# eBike_Controller_v2.net
KiCad netlist of a schematic drawn in EAGLE
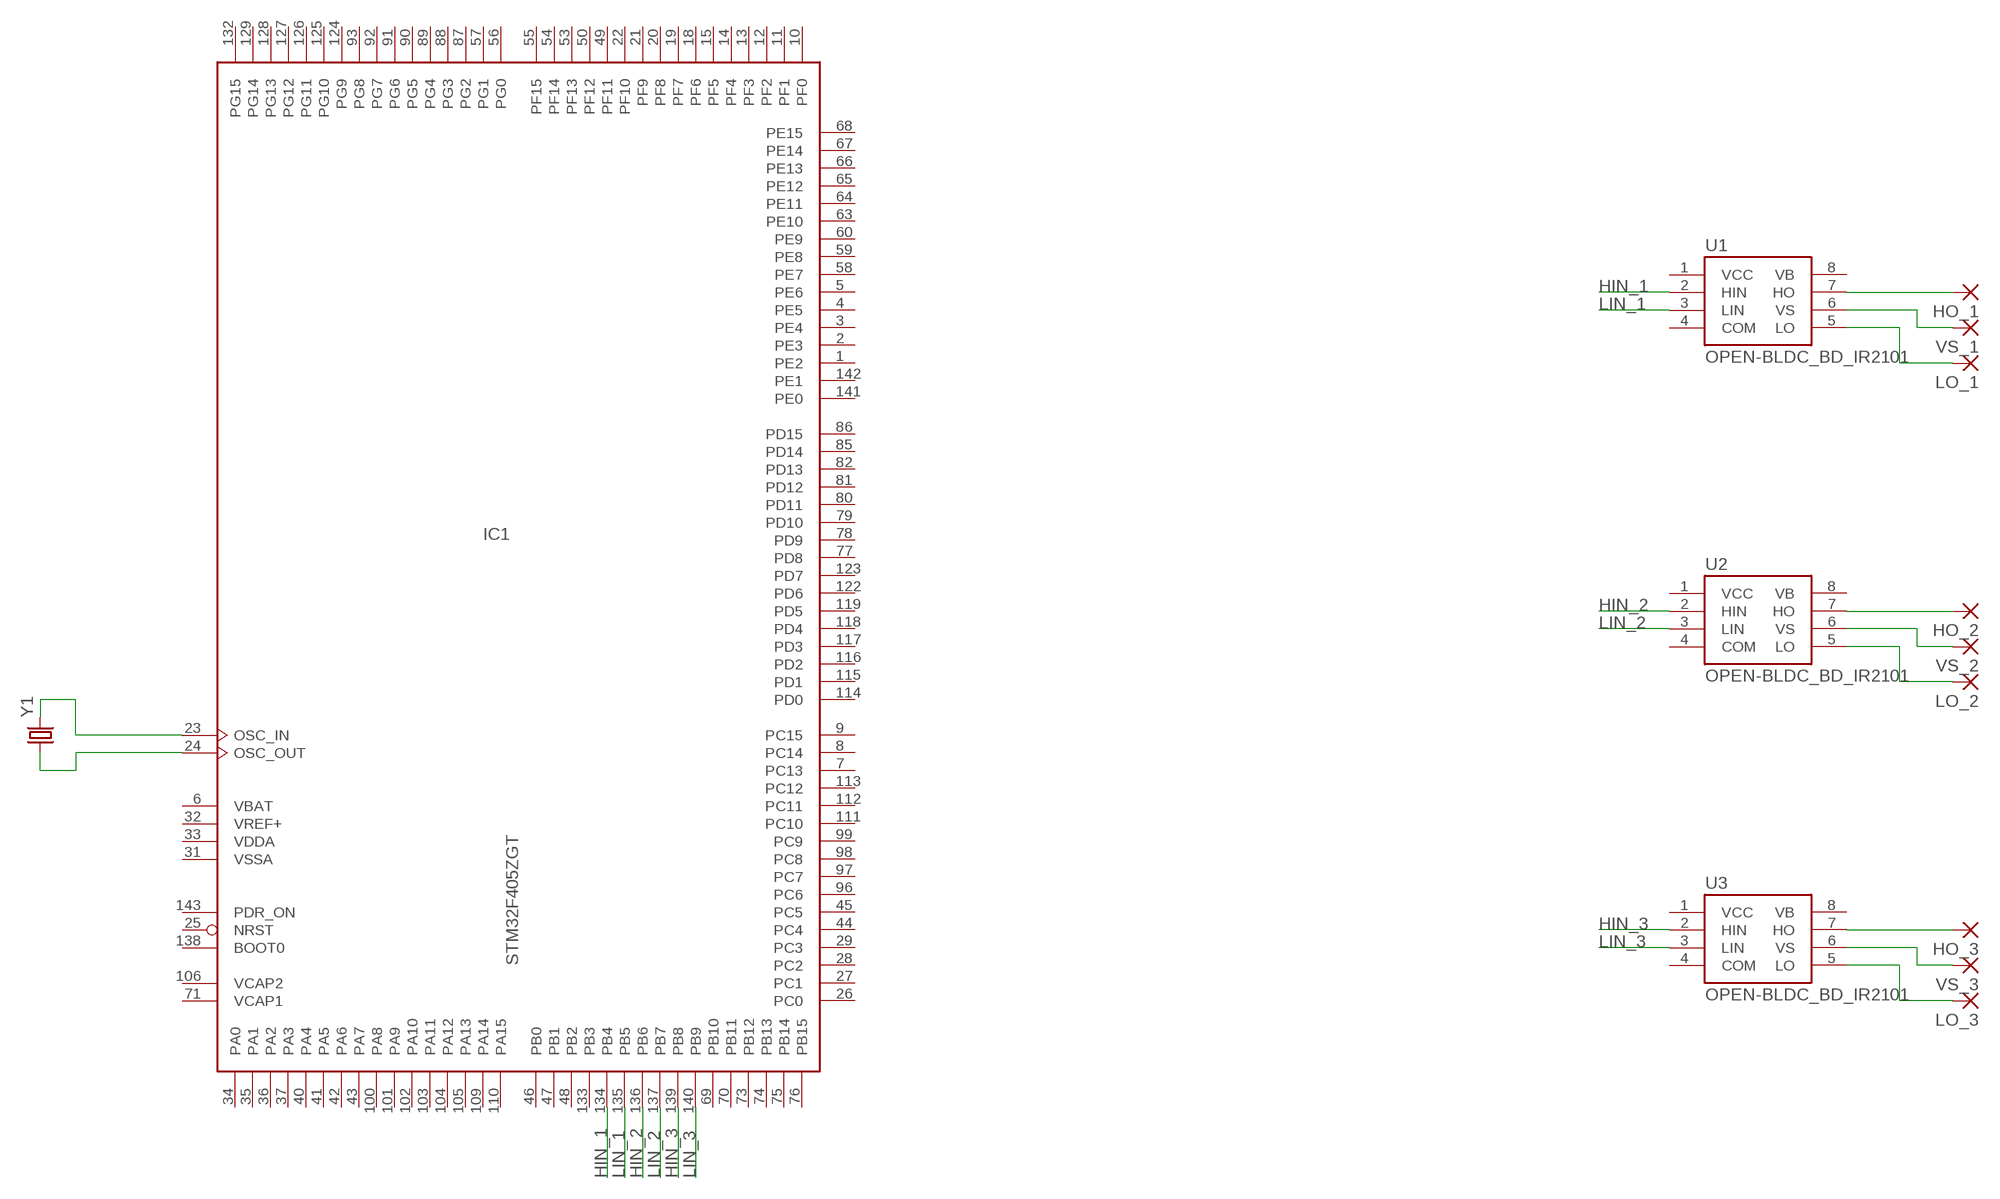
[diagram p0: schematic, sheet 1]

(export (version "E")
  (design (tool "Eeschema 10.0.6"))
  (components
    (comp (ref "HO_1")
      (value "3,81/1,4")
      (footprint "eagle-import:3,81_1,4")
      (libsource (lib "eagle-import") (part "3,81/1,4"))
    )
    (comp (ref "HO_2")
      (value "3,81/1,4")
      (footprint "eagle-import:3,81_1,4")
      (libsource (lib "eagle-import") (part "3,81/1,4"))
    )
    (comp (ref "HO_3")
      (value "3,81/1,4")
      (footprint "eagle-import:3,81_1,4")
      (libsource (lib "eagle-import") (part "3,81/1,4"))
    )
    (comp (ref "IC1")
      (value "STM32F405ZGT")
      (footprint "eagle-import:LQFP144")
      (libsource (lib "eagle-import") (part "STM32F405ZTG"))
    )
    (comp (ref "LO_1")
      (value "3,81/1,4")
      (footprint "eagle-import:3,81_1,4")
      (libsource (lib "eagle-import") (part "3,81/1,4"))
    )
    (comp (ref "LO_2")
      (value "3,81/1,4")
      (footprint "eagle-import:3,81_1,4")
      (libsource (lib "eagle-import") (part "3,81/1,4"))
    )
    (comp (ref "LO_3")
      (value "3,81/1,4")
      (footprint "eagle-import:3,81_1,4")
      (libsource (lib "eagle-import") (part "3,81/1,4"))
    )
    (comp (ref "U1")
      (value "OPEN-BLDC_BD_IR2101")
      (footprint "eagle-import:OPEN-BLDC_SO8")
      (libsource (lib "eagle-import") (part "OPEN-BLDC_BD_IR2101"))
    )
    (comp (ref "U2")
      (value "OPEN-BLDC_BD_IR2101")
      (footprint "eagle-import:OPEN-BLDC_SO8")
      (libsource (lib "eagle-import") (part "OPEN-BLDC_BD_IR2101"))
    )
    (comp (ref "U3")
      (value "OPEN-BLDC_BD_IR2101")
      (footprint "eagle-import:OPEN-BLDC_SO8")
      (libsource (lib "eagle-import") (part "OPEN-BLDC_BD_IR2101"))
    )
    (comp (ref "VS_1")
      (value "3,81/1,4")
      (footprint "eagle-import:3,81_1,4")
      (libsource (lib "eagle-import") (part "3,81/1,4"))
    )
    (comp (ref "VS_2")
      (value "3,81/1,4")
      (footprint "eagle-import:3,81_1,4")
      (libsource (lib "eagle-import") (part "3,81/1,4"))
    )
    (comp (ref "VS_3")
      (value "3,81/1,4")
      (footprint "eagle-import:3,81_1,4")
      (libsource (lib "eagle-import") (part "3,81/1,4"))
    )
    (comp (ref "Y1")
      (value "CRYSTALHC49US")
      (footprint "eagle-import:HC49US")
      (libsource (lib "eagle-import") (part "CRYSTALHC49US"))
    )
  )
  (nets
    (net (code "1") (name "/HIN_1") (class "Default")
      (node (ref "IC1") (pin "134") (pinfunction "PB4_134") (pintype "bidirectional"))
      (node (ref "U1") (pin "2") (pinfunction "HIN_2") (pintype "bidirectional"))
    )
    (net (code "2") (name "/HIN_2") (class "Default")
      (node (ref "IC1") (pin "136") (pinfunction "PB6_136") (pintype "bidirectional"))
      (node (ref "U2") (pin "2") (pinfunction "HIN_2") (pintype "bidirectional"))
    )
    (net (code "3") (name "/HIN_3") (class "Default")
      (node (ref "IC1") (pin "139") (pinfunction "PB8_139") (pintype "bidirectional"))
      (node (ref "U3") (pin "2") (pinfunction "HIN_2") (pintype "bidirectional"))
    )
    (net (code "4") (name "/LIN_1") (class "Default")
      (node (ref "IC1") (pin "135") (pinfunction "PB5_135") (pintype "bidirectional"))
      (node (ref "U1") (pin "3") (pinfunction "LIN_3") (pintype "bidirectional"))
    )
    (net (code "5") (name "/LIN_2") (class "Default")
      (node (ref "IC1") (pin "137") (pinfunction "PB7_137") (pintype "bidirectional"))
      (node (ref "U2") (pin "3") (pinfunction "LIN_3") (pintype "bidirectional"))
    )
    (net (code "6") (name "/LIN_3") (class "Default")
      (node (ref "IC1") (pin "140") (pinfunction "PB9_140") (pintype "bidirectional"))
      (node (ref "U3") (pin "3") (pinfunction "LIN_3") (pintype "bidirectional"))
    )
    (net (code "7") (name "/VBAT") (class "Default")
      (node (ref "IC1") (pin "6") (pinfunction "VBAT_6") (pintype "power_in"))
    )
    (net (code "8") (name "/VCAP1") (class "Default")
      (node (ref "IC1") (pin "71") (pinfunction "VCAP1_71") (pintype "power_in"))
    )
    (net (code "9") (name "/VCAP2") (class "Default")
      (node (ref "IC1") (pin "106") (pinfunction "VCAP2_106") (pintype "power_in"))
    )
    (net (code "10") (name "/VDDA") (class "Default")
      (node (ref "IC1") (pin "33") (pinfunction "VDDA_33") (pintype "power_in"))
    )
    (net (code "11") (name "/VREF+") (class "Default")
      (node (ref "IC1") (pin "32") (pinfunction "VREF+_32") (pintype "power_in"))
    )
    (net (code "12") (name "/VSSA") (class "Default")
      (node (ref "IC1") (pin "31") (pinfunction "VSSA_31") (pintype "power_in"))
    )
    (net (code "13") (name "Net-(HO_1-P)") (class "Default")
      (node (ref "HO_1") (pin "1") (pinfunction "P_1") (pintype "passive"))
      (node (ref "U1") (pin "7") (pinfunction "HO_7") (pintype "bidirectional"))
    )
    (net (code "14") (name "Net-(HO_2-P)") (class "Default")
      (node (ref "HO_2") (pin "1") (pinfunction "P_1") (pintype "passive"))
      (node (ref "U2") (pin "7") (pinfunction "HO_7") (pintype "bidirectional"))
    )
    (net (code "15") (name "Net-(HO_3-P)") (class "Default")
      (node (ref "HO_3") (pin "1") (pinfunction "P_1") (pintype "passive"))
      (node (ref "U3") (pin "7") (pinfunction "HO_7") (pintype "bidirectional"))
    )
    (net (code "16") (name "Net-(IC1A-OSC_IN)") (class "Default")
      (node (ref "IC1") (pin "23") (pinfunction "OSC_IN_23") (pintype "bidirectional"))
      (node (ref "Y1") (pin "2") (pinfunction "2_2") (pintype "passive"))
    )
    (net (code "17") (name "Net-(IC1A-OSC_OUT)") (class "Default")
      (node (ref "IC1") (pin "24") (pinfunction "OSC_OUT_24") (pintype "bidirectional"))
      (node (ref "Y1") (pin "1") (pinfunction "1_1") (pintype "passive"))
    )
    (net (code "18") (name "Net-(LO_1-P)") (class "Default")
      (node (ref "LO_1") (pin "1") (pinfunction "P_1") (pintype "passive"))
      (node (ref "U1") (pin "5") (pinfunction "LO_5") (pintype "bidirectional"))
    )
    (net (code "19") (name "Net-(LO_2-P)") (class "Default")
      (node (ref "LO_2") (pin "1") (pinfunction "P_1") (pintype "passive"))
      (node (ref "U2") (pin "5") (pinfunction "LO_5") (pintype "bidirectional"))
    )
    (net (code "20") (name "Net-(LO_3-P)") (class "Default")
      (node (ref "LO_3") (pin "1") (pinfunction "P_1") (pintype "passive"))
      (node (ref "U3") (pin "5") (pinfunction "LO_5") (pintype "bidirectional"))
    )
    (net (code "21") (name "Net-(U1-VS)") (class "Default")
      (node (ref "U1") (pin "6") (pinfunction "VS_6") (pintype "bidirectional"))
      (node (ref "VS_1") (pin "1") (pinfunction "P_1") (pintype "passive"))
    )
    (net (code "22") (name "Net-(U2-VS)") (class "Default")
      (node (ref "U2") (pin "6") (pinfunction "VS_6") (pintype "bidirectional"))
      (node (ref "VS_2") (pin "1") (pinfunction "P_1") (pintype "passive"))
    )
    (net (code "23") (name "Net-(U3-VS)") (class "Default")
      (node (ref "U3") (pin "6") (pinfunction "VS_6") (pintype "bidirectional"))
      (node (ref "VS_3") (pin "1") (pinfunction "P_1") (pintype "passive"))
    )
    (net (code "24") (name "unconnected-(IC1A-BOOT0-Pad138)") (class "Default")
      (node (ref "IC1") (pin "138") (pinfunction "BOOT0_138") (pintype "input"))
    )
    (net (code "25") (name "unconnected-(IC1A-NRST-Pad25)") (class "Default")
      (node (ref "IC1") (pin "25") (pinfunction "NRST_25") (pintype "bidirectional"))
    )
    (net (code "26") (name "unconnected-(IC1A-PA0-Pad34)") (class "Default")
      (node (ref "IC1") (pin "34") (pinfunction "PA0_34") (pintype "bidirectional"))
    )
    (net (code "27") (name "unconnected-(IC1A-PA1-Pad35)") (class "Default")
      (node (ref "IC1") (pin "35") (pinfunction "PA1_35") (pintype "bidirectional"))
    )
    (net (code "28") (name "unconnected-(IC1A-PA2-Pad36)") (class "Default")
      (node (ref "IC1") (pin "36") (pinfunction "PA2_36") (pintype "bidirectional"))
    )
    (net (code "29") (name "unconnected-(IC1A-PA3-Pad37)") (class "Default")
      (node (ref "IC1") (pin "37") (pinfunction "PA3_37") (pintype "bidirectional"))
    )
    (net (code "30") (name "unconnected-(IC1A-PA4-Pad40)") (class "Default")
      (node (ref "IC1") (pin "40") (pinfunction "PA4_40") (pintype "bidirectional"))
    )
    (net (code "31") (name "unconnected-(IC1A-PA5-Pad41)") (class "Default")
      (node (ref "IC1") (pin "41") (pinfunction "PA5_41") (pintype "bidirectional"))
    )
    (net (code "32") (name "unconnected-(IC1A-PA6-Pad42)") (class "Default")
      (node (ref "IC1") (pin "42") (pinfunction "PA6_42") (pintype "bidirectional"))
    )
    (net (code "33") (name "unconnected-(IC1A-PA7-Pad43)") (class "Default")
      (node (ref "IC1") (pin "43") (pinfunction "PA7_43") (pintype "bidirectional"))
    )
    (net (code "34") (name "unconnected-(IC1A-PA8-Pad100)") (class "Default")
      (node (ref "IC1") (pin "100") (pinfunction "PA8_100") (pintype "bidirectional"))
    )
    (net (code "35") (name "unconnected-(IC1A-PA9-Pad101)") (class "Default")
      (node (ref "IC1") (pin "101") (pinfunction "PA9_101") (pintype "bidirectional"))
    )
    (net (code "36") (name "unconnected-(IC1A-PA10-Pad102)") (class "Default")
      (node (ref "IC1") (pin "102") (pinfunction "PA10_102") (pintype "bidirectional"))
    )
    (net (code "37") (name "unconnected-(IC1A-PA11-Pad103)") (class "Default")
      (node (ref "IC1") (pin "103") (pinfunction "PA11_103") (pintype "bidirectional"))
    )
    (net (code "38") (name "unconnected-(IC1A-PA12-Pad104)") (class "Default")
      (node (ref "IC1") (pin "104") (pinfunction "PA12_104") (pintype "bidirectional"))
    )
    (net (code "39") (name "unconnected-(IC1A-PA13-Pad105)") (class "Default")
      (node (ref "IC1") (pin "105") (pinfunction "PA13_105") (pintype "bidirectional"))
    )
    (net (code "40") (name "unconnected-(IC1A-PA14-Pad109)") (class "Default")
      (node (ref "IC1") (pin "109") (pinfunction "PA14_109") (pintype "bidirectional"))
    )
    (net (code "41") (name "unconnected-(IC1A-PA15-Pad110)") (class "Default")
      (node (ref "IC1") (pin "110") (pinfunction "PA15_110") (pintype "bidirectional"))
    )
    (net (code "42") (name "unconnected-(IC1A-PB0-Pad46)") (class "Default")
      (node (ref "IC1") (pin "46") (pinfunction "PB0_46") (pintype "bidirectional"))
    )
    (net (code "43") (name "unconnected-(IC1A-PB1-Pad47)") (class "Default")
      (node (ref "IC1") (pin "47") (pinfunction "PB1_47") (pintype "bidirectional"))
    )
    (net (code "44") (name "unconnected-(IC1A-PB2-Pad48)") (class "Default")
      (node (ref "IC1") (pin "48") (pinfunction "PB2_48") (pintype "bidirectional"))
    )
    (net (code "45") (name "unconnected-(IC1A-PB3-Pad133)") (class "Default")
      (node (ref "IC1") (pin "133") (pinfunction "PB3_133") (pintype "bidirectional"))
    )
    (net (code "46") (name "unconnected-(IC1A-PB10-Pad69)") (class "Default")
      (node (ref "IC1") (pin "69") (pinfunction "PB10_69") (pintype "bidirectional"))
    )
    (net (code "47") (name "unconnected-(IC1A-PB11-Pad70)") (class "Default")
      (node (ref "IC1") (pin "70") (pinfunction "PB11_70") (pintype "bidirectional"))
    )
    (net (code "48") (name "unconnected-(IC1A-PB12-Pad73)") (class "Default")
      (node (ref "IC1") (pin "73") (pinfunction "PB12_73") (pintype "bidirectional"))
    )
    (net (code "49") (name "unconnected-(IC1A-PB13-Pad74)") (class "Default")
      (node (ref "IC1") (pin "74") (pinfunction "PB13_74") (pintype "bidirectional"))
    )
    (net (code "50") (name "unconnected-(IC1A-PB14-Pad75)") (class "Default")
      (node (ref "IC1") (pin "75") (pinfunction "PB14_75") (pintype "bidirectional"))
    )
    (net (code "51") (name "unconnected-(IC1A-PB15-Pad76)") (class "Default")
      (node (ref "IC1") (pin "76") (pinfunction "PB15_76") (pintype "bidirectional"))
    )
    (net (code "52") (name "unconnected-(IC1A-PC0-Pad26)") (class "Default")
      (node (ref "IC1") (pin "26") (pinfunction "PC0_26") (pintype "bidirectional"))
    )
    (net (code "53") (name "unconnected-(IC1A-PC1-Pad27)") (class "Default")
      (node (ref "IC1") (pin "27") (pinfunction "PC1_27") (pintype "bidirectional"))
    )
    (net (code "54") (name "unconnected-(IC1A-PC2-Pad28)") (class "Default")
      (node (ref "IC1") (pin "28") (pinfunction "PC2_28") (pintype "bidirectional"))
    )
    (net (code "55") (name "unconnected-(IC1A-PC3-Pad29)") (class "Default")
      (node (ref "IC1") (pin "29") (pinfunction "PC3_29") (pintype "bidirectional"))
    )
    (net (code "56") (name "unconnected-(IC1A-PC4-Pad44)") (class "Default")
      (node (ref "IC1") (pin "44") (pinfunction "PC4_44") (pintype "bidirectional"))
    )
    (net (code "57") (name "unconnected-(IC1A-PC5-Pad45)") (class "Default")
      (node (ref "IC1") (pin "45") (pinfunction "PC5_45") (pintype "bidirectional"))
    )
    (net (code "58") (name "unconnected-(IC1A-PC6-Pad96)") (class "Default")
      (node (ref "IC1") (pin "96") (pinfunction "PC6_96") (pintype "bidirectional"))
    )
    (net (code "59") (name "unconnected-(IC1A-PC7-Pad97)") (class "Default")
      (node (ref "IC1") (pin "97") (pinfunction "PC7_97") (pintype "bidirectional"))
    )
    (net (code "60") (name "unconnected-(IC1A-PC8-Pad98)") (class "Default")
      (node (ref "IC1") (pin "98") (pinfunction "PC8_98") (pintype "bidirectional"))
    )
    (net (code "61") (name "unconnected-(IC1A-PC9-Pad99)") (class "Default")
      (node (ref "IC1") (pin "99") (pinfunction "PC9_99") (pintype "bidirectional"))
    )
    (net (code "62") (name "unconnected-(IC1A-PC10-Pad111)") (class "Default")
      (node (ref "IC1") (pin "111") (pinfunction "PC10_111") (pintype "bidirectional"))
    )
    (net (code "63") (name "unconnected-(IC1A-PC11-Pad112)") (class "Default")
      (node (ref "IC1") (pin "112") (pinfunction "PC11_112") (pintype "bidirectional"))
    )
    (net (code "64") (name "unconnected-(IC1A-PC12-Pad113)") (class "Default")
      (node (ref "IC1") (pin "113") (pinfunction "PC12_113") (pintype "bidirectional"))
    )
    (net (code "65") (name "unconnected-(IC1A-PC13-Pad7)") (class "Default")
      (node (ref "IC1") (pin "7") (pinfunction "PC13_7") (pintype "bidirectional"))
    )
    (net (code "66") (name "unconnected-(IC1A-PC14-Pad8)") (class "Default")
      (node (ref "IC1") (pin "8") (pinfunction "PC14_8") (pintype "bidirectional"))
    )
    (net (code "67") (name "unconnected-(IC1A-PC15-Pad9)") (class "Default")
      (node (ref "IC1") (pin "9") (pinfunction "PC15_9") (pintype "bidirectional"))
    )
    (net (code "68") (name "unconnected-(IC1A-PD0-Pad114)") (class "Default")
      (node (ref "IC1") (pin "114") (pinfunction "PD0_114") (pintype "bidirectional"))
    )
    (net (code "69") (name "unconnected-(IC1A-PD1-Pad115)") (class "Default")
      (node (ref "IC1") (pin "115") (pinfunction "PD1_115") (pintype "bidirectional"))
    )
    (net (code "70") (name "unconnected-(IC1A-PD2-Pad116)") (class "Default")
      (node (ref "IC1") (pin "116") (pinfunction "PD2_116") (pintype "bidirectional"))
    )
    (net (code "71") (name "unconnected-(IC1A-PD3-Pad117)") (class "Default")
      (node (ref "IC1") (pin "117") (pinfunction "PD3_117") (pintype "bidirectional"))
    )
    (net (code "72") (name "unconnected-(IC1A-PD4-Pad118)") (class "Default")
      (node (ref "IC1") (pin "118") (pinfunction "PD4_118") (pintype "bidirectional"))
    )
    (net (code "73") (name "unconnected-(IC1A-PD5-Pad119)") (class "Default")
      (node (ref "IC1") (pin "119") (pinfunction "PD5_119") (pintype "bidirectional"))
    )
    (net (code "74") (name "unconnected-(IC1A-PD6-Pad122)") (class "Default")
      (node (ref "IC1") (pin "122") (pinfunction "PD6_122") (pintype "bidirectional"))
    )
    (net (code "75") (name "unconnected-(IC1A-PD7-Pad123)") (class "Default")
      (node (ref "IC1") (pin "123") (pinfunction "PD7_123") (pintype "bidirectional"))
    )
    (net (code "76") (name "unconnected-(IC1A-PD8-Pad77)") (class "Default")
      (node (ref "IC1") (pin "77") (pinfunction "PD8_77") (pintype "bidirectional"))
    )
    (net (code "77") (name "unconnected-(IC1A-PD9-Pad78)") (class "Default")
      (node (ref "IC1") (pin "78") (pinfunction "PD9_78") (pintype "bidirectional"))
    )
    (net (code "78") (name "unconnected-(IC1A-PD10-Pad79)") (class "Default")
      (node (ref "IC1") (pin "79") (pinfunction "PD10_79") (pintype "bidirectional"))
    )
    (net (code "79") (name "unconnected-(IC1A-PD11-Pad80)") (class "Default")
      (node (ref "IC1") (pin "80") (pinfunction "PD11_80") (pintype "bidirectional"))
    )
    (net (code "80") (name "unconnected-(IC1A-PD12-Pad81)") (class "Default")
      (node (ref "IC1") (pin "81") (pinfunction "PD12_81") (pintype "bidirectional"))
    )
    (net (code "81") (name "unconnected-(IC1A-PD13-Pad82)") (class "Default")
      (node (ref "IC1") (pin "82") (pinfunction "PD13_82") (pintype "bidirectional"))
    )
    (net (code "82") (name "unconnected-(IC1A-PD14-Pad85)") (class "Default")
      (node (ref "IC1") (pin "85") (pinfunction "PD14_85") (pintype "bidirectional"))
    )
    (net (code "83") (name "unconnected-(IC1A-PD15-Pad86)") (class "Default")
      (node (ref "IC1") (pin "86") (pinfunction "PD15_86") (pintype "bidirectional"))
    )
    (net (code "84") (name "unconnected-(IC1A-PDR_ON-Pad143)") (class "Default")
      (node (ref "IC1") (pin "143") (pinfunction "PDR_ON_143") (pintype "input"))
    )
    (net (code "85") (name "unconnected-(IC1A-PE0-Pad141)") (class "Default")
      (node (ref "IC1") (pin "141") (pinfunction "PE0_141") (pintype "bidirectional"))
    )
    (net (code "86") (name "unconnected-(IC1A-PE1-Pad142)") (class "Default")
      (node (ref "IC1") (pin "142") (pinfunction "PE1_142") (pintype "bidirectional"))
    )
    (net (code "87") (name "unconnected-(IC1A-PE2-Pad1)") (class "Default")
      (node (ref "IC1") (pin "1") (pinfunction "PE2_1") (pintype "bidirectional"))
    )
    (net (code "88") (name "unconnected-(IC1A-PE3-Pad2)") (class "Default")
      (node (ref "IC1") (pin "2") (pinfunction "PE3_2") (pintype "bidirectional"))
    )
    (net (code "89") (name "unconnected-(IC1A-PE4-Pad3)") (class "Default")
      (node (ref "IC1") (pin "3") (pinfunction "PE4_3") (pintype "bidirectional"))
    )
    (net (code "90") (name "unconnected-(IC1A-PE5-Pad4)") (class "Default")
      (node (ref "IC1") (pin "4") (pinfunction "PE5_4") (pintype "bidirectional"))
    )
    (net (code "91") (name "unconnected-(IC1A-PE6-Pad5)") (class "Default")
      (node (ref "IC1") (pin "5") (pinfunction "PE6_5") (pintype "bidirectional"))
    )
    (net (code "92") (name "unconnected-(IC1A-PE7-Pad58)") (class "Default")
      (node (ref "IC1") (pin "58") (pinfunction "PE7_58") (pintype "bidirectional"))
    )
    (net (code "93") (name "unconnected-(IC1A-PE8-Pad59)") (class "Default")
      (node (ref "IC1") (pin "59") (pinfunction "PE8_59") (pintype "bidirectional"))
    )
    (net (code "94") (name "unconnected-(IC1A-PE9-Pad60)") (class "Default")
      (node (ref "IC1") (pin "60") (pinfunction "PE9_60") (pintype "bidirectional"))
    )
    (net (code "95") (name "unconnected-(IC1A-PE10-Pad63)") (class "Default")
      (node (ref "IC1") (pin "63") (pinfunction "PE10_63") (pintype "bidirectional"))
    )
    (net (code "96") (name "unconnected-(IC1A-PE11-Pad64)") (class "Default")
      (node (ref "IC1") (pin "64") (pinfunction "PE11_64") (pintype "bidirectional"))
    )
    (net (code "97") (name "unconnected-(IC1A-PE12-Pad65)") (class "Default")
      (node (ref "IC1") (pin "65") (pinfunction "PE12_65") (pintype "bidirectional"))
    )
    (net (code "98") (name "unconnected-(IC1A-PE13-Pad66)") (class "Default")
      (node (ref "IC1") (pin "66") (pinfunction "PE13_66") (pintype "bidirectional"))
    )
    (net (code "99") (name "unconnected-(IC1A-PE14-Pad67)") (class "Default")
      (node (ref "IC1") (pin "67") (pinfunction "PE14_67") (pintype "bidirectional"))
    )
    (net (code "100") (name "unconnected-(IC1A-PE15-Pad68)") (class "Default")
      (node (ref "IC1") (pin "68") (pinfunction "PE15_68") (pintype "bidirectional"))
    )
    (net (code "101") (name "unconnected-(IC1A-PF0-Pad10)") (class "Default")
      (node (ref "IC1") (pin "10") (pinfunction "PF0_10") (pintype "bidirectional"))
    )
    (net (code "102") (name "unconnected-(IC1A-PF1-Pad11)") (class "Default")
      (node (ref "IC1") (pin "11") (pinfunction "PF1_11") (pintype "bidirectional"))
    )
    (net (code "103") (name "unconnected-(IC1A-PF2-Pad12)") (class "Default")
      (node (ref "IC1") (pin "12") (pinfunction "PF2_12") (pintype "bidirectional"))
    )
    (net (code "104") (name "unconnected-(IC1A-PF3-Pad13)") (class "Default")
      (node (ref "IC1") (pin "13") (pinfunction "PF3_13") (pintype "bidirectional"))
    )
    (net (code "105") (name "unconnected-(IC1A-PF4-Pad14)") (class "Default")
      (node (ref "IC1") (pin "14") (pinfunction "PF4_14") (pintype "bidirectional"))
    )
    (net (code "106") (name "unconnected-(IC1A-PF5-Pad15)") (class "Default")
      (node (ref "IC1") (pin "15") (pinfunction "PF5_15") (pintype "bidirectional"))
    )
    (net (code "107") (name "unconnected-(IC1A-PF6-Pad18)") (class "Default")
      (node (ref "IC1") (pin "18") (pinfunction "PF6_18") (pintype "bidirectional"))
    )
    (net (code "108") (name "unconnected-(IC1A-PF7-Pad19)") (class "Default")
      (node (ref "IC1") (pin "19") (pinfunction "PF7_19") (pintype "bidirectional"))
    )
    (net (code "109") (name "unconnected-(IC1A-PF8-Pad20)") (class "Default")
      (node (ref "IC1") (pin "20") (pinfunction "PF8_20") (pintype "bidirectional"))
    )
    (net (code "110") (name "unconnected-(IC1A-PF9-Pad21)") (class "Default")
      (node (ref "IC1") (pin "21") (pinfunction "PF9_21") (pintype "bidirectional"))
    )
    (net (code "111") (name "unconnected-(IC1A-PF10-Pad22)") (class "Default")
      (node (ref "IC1") (pin "22") (pinfunction "PF10_22") (pintype "bidirectional"))
    )
    (net (code "112") (name "unconnected-(IC1A-PF11-Pad49)") (class "Default")
      (node (ref "IC1") (pin "49") (pinfunction "PF11_49") (pintype "bidirectional"))
    )
    (net (code "113") (name "unconnected-(IC1A-PF12-Pad50)") (class "Default")
      (node (ref "IC1") (pin "50") (pinfunction "PF12_50") (pintype "bidirectional"))
    )
    (net (code "114") (name "unconnected-(IC1A-PF13-Pad53)") (class "Default")
      (node (ref "IC1") (pin "53") (pinfunction "PF13_53") (pintype "bidirectional"))
    )
    (net (code "115") (name "unconnected-(IC1A-PF14-Pad54)") (class "Default")
      (node (ref "IC1") (pin "54") (pinfunction "PF14_54") (pintype "bidirectional"))
    )
    (net (code "116") (name "unconnected-(IC1A-PF15-Pad55)") (class "Default")
      (node (ref "IC1") (pin "55") (pinfunction "PF15_55") (pintype "bidirectional"))
    )
    (net (code "117") (name "unconnected-(IC1A-PG0-Pad56)") (class "Default")
      (node (ref "IC1") (pin "56") (pinfunction "PG0_56") (pintype "bidirectional"))
    )
    (net (code "118") (name "unconnected-(IC1A-PG1-Pad57)") (class "Default")
      (node (ref "IC1") (pin "57") (pinfunction "PG1_57") (pintype "bidirectional"))
    )
    (net (code "119") (name "unconnected-(IC1A-PG2-Pad87)") (class "Default")
      (node (ref "IC1") (pin "87") (pinfunction "PG2_87") (pintype "bidirectional"))
    )
    (net (code "120") (name "unconnected-(IC1A-PG3-Pad88)") (class "Default")
      (node (ref "IC1") (pin "88") (pinfunction "PG3_88") (pintype "bidirectional"))
    )
    (net (code "121") (name "unconnected-(IC1A-PG4-Pad89)") (class "Default")
      (node (ref "IC1") (pin "89") (pinfunction "PG4_89") (pintype "bidirectional"))
    )
    (net (code "122") (name "unconnected-(IC1A-PG5-Pad90)") (class "Default")
      (node (ref "IC1") (pin "90") (pinfunction "PG5_90") (pintype "bidirectional"))
    )
    (net (code "123") (name "unconnected-(IC1A-PG6-Pad91)") (class "Default")
      (node (ref "IC1") (pin "91") (pinfunction "PG6_91") (pintype "bidirectional"))
    )
    (net (code "124") (name "unconnected-(IC1A-PG7-Pad92)") (class "Default")
      (node (ref "IC1") (pin "92") (pinfunction "PG7_92") (pintype "bidirectional"))
    )
    (net (code "125") (name "unconnected-(IC1A-PG8-Pad93)") (class "Default")
      (node (ref "IC1") (pin "93") (pinfunction "PG8_93") (pintype "bidirectional"))
    )
    (net (code "126") (name "unconnected-(IC1A-PG9-Pad124)") (class "Default")
      (node (ref "IC1") (pin "124") (pinfunction "PG9_124") (pintype "bidirectional"))
    )
    (net (code "127") (name "unconnected-(IC1A-PG10-Pad125)") (class "Default")
      (node (ref "IC1") (pin "125") (pinfunction "PG10_125") (pintype "bidirectional"))
    )
    (net (code "128") (name "unconnected-(IC1A-PG11-Pad126)") (class "Default")
      (node (ref "IC1") (pin "126") (pinfunction "PG11_126") (pintype "bidirectional"))
    )
    (net (code "129") (name "unconnected-(IC1A-PG12-Pad127)") (class "Default")
      (node (ref "IC1") (pin "127") (pinfunction "PG12_127") (pintype "bidirectional"))
    )
    (net (code "130") (name "unconnected-(IC1A-PG13-Pad128)") (class "Default")
      (node (ref "IC1") (pin "128") (pinfunction "PG13_128") (pintype "bidirectional"))
    )
    (net (code "131") (name "unconnected-(IC1A-PG14-Pad129)") (class "Default")
      (node (ref "IC1") (pin "129") (pinfunction "PG14_129") (pintype "bidirectional"))
    )
    (net (code "132") (name "unconnected-(IC1A-PG15-Pad132)") (class "Default")
      (node (ref "IC1") (pin "132") (pinfunction "PG15_132") (pintype "bidirectional"))
    )
    (net (code "133") (name "unconnected-(U1-COM-Pad4)") (class "Default")
      (node (ref "U1") (pin "4") (pinfunction "COM_4") (pintype "bidirectional"))
    )
    (net (code "134") (name "unconnected-(U1-VB-Pad8)") (class "Default")
      (node (ref "U1") (pin "8") (pinfunction "VB_8") (pintype "bidirectional"))
    )
    (net (code "135") (name "unconnected-(U1-VCC-Pad1)") (class "Default")
      (node (ref "U1") (pin "1") (pinfunction "VCC_1") (pintype "bidirectional"))
    )
    (net (code "136") (name "unconnected-(U2-COM-Pad4)") (class "Default")
      (node (ref "U2") (pin "4") (pinfunction "COM_4") (pintype "bidirectional"))
    )
    (net (code "137") (name "unconnected-(U2-VB-Pad8)") (class "Default")
      (node (ref "U2") (pin "8") (pinfunction "VB_8") (pintype "bidirectional"))
    )
    (net (code "138") (name "unconnected-(U2-VCC-Pad1)") (class "Default")
      (node (ref "U2") (pin "1") (pinfunction "VCC_1") (pintype "bidirectional"))
    )
    (net (code "139") (name "unconnected-(U3-COM-Pad4)") (class "Default")
      (node (ref "U3") (pin "4") (pinfunction "COM_4") (pintype "bidirectional"))
    )
    (net (code "140") (name "unconnected-(U3-VB-Pad8)") (class "Default")
      (node (ref "U3") (pin "8") (pinfunction "VB_8") (pintype "bidirectional"))
    )
    (net (code "141") (name "unconnected-(U3-VCC-Pad1)") (class "Default")
      (node (ref "U3") (pin "1") (pinfunction "VCC_1") (pintype "bidirectional"))
    )
  )
)
